# protocoles_de_comm.net
KiCad netlist of a schematic drawn in Altium Designer
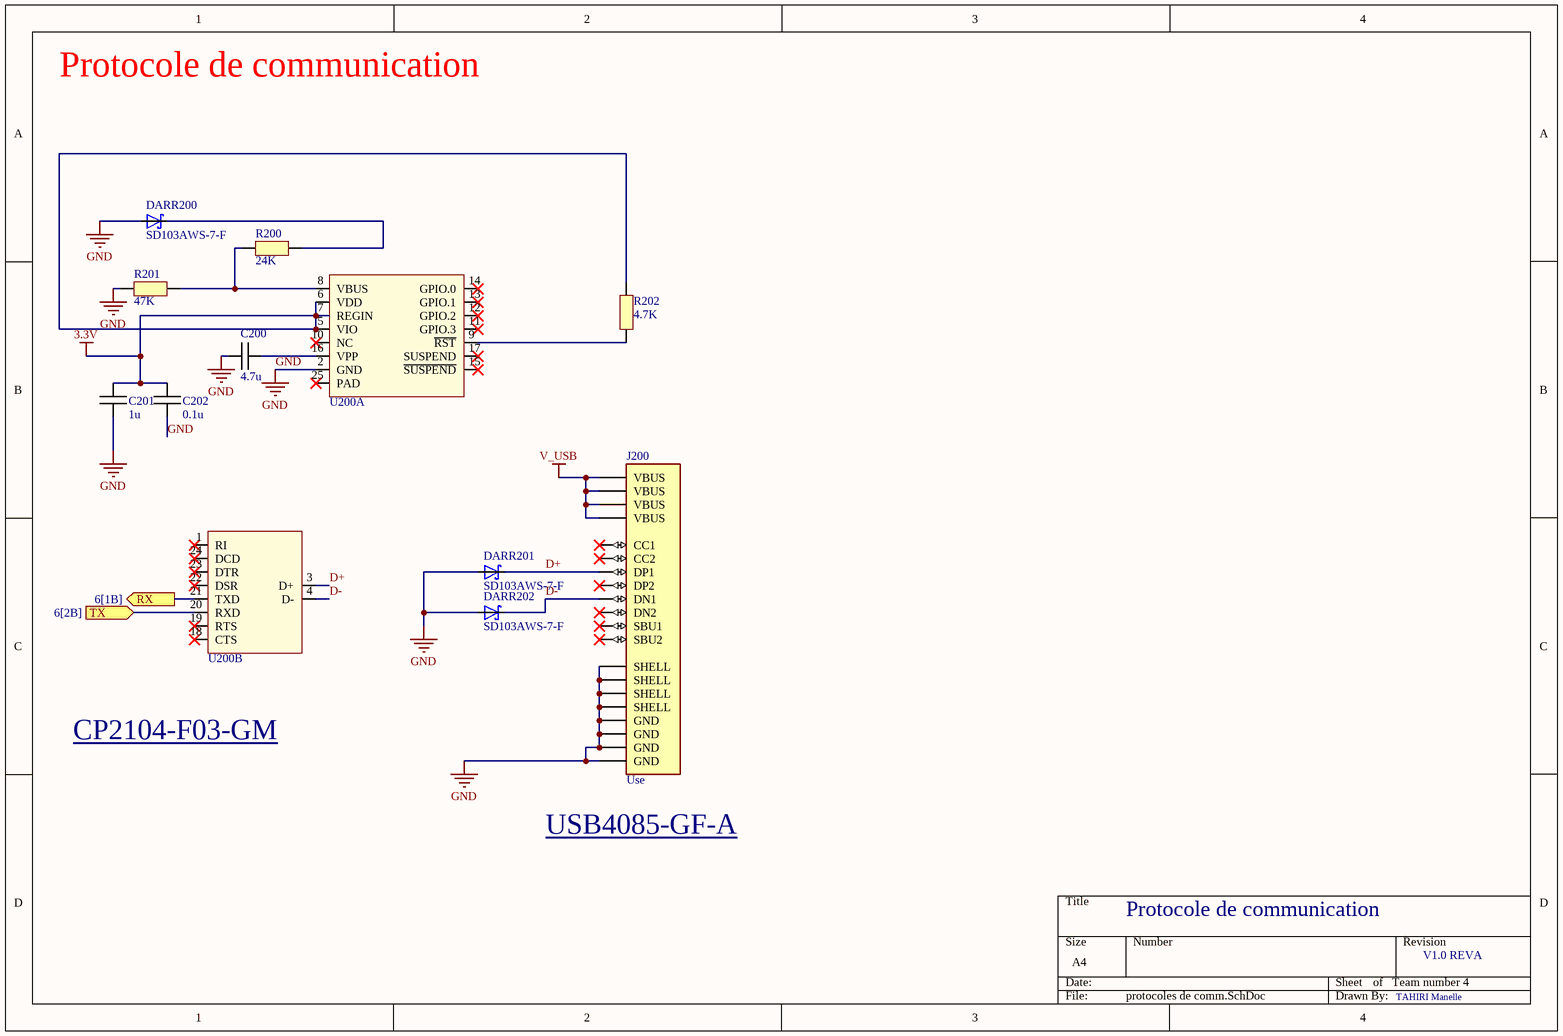
[diagram p0: protocoles de comm.SchDoc]

(export (version "E")
  (design (tool "Eeschema 10.0.6"))
  (components
    (comp (ref "C200")
      (value "4.7u")
      (footprint "CAPC1005X06N")
      (libsource (lib "SCHLibrary") (part "Capacitor"))
    )
    (comp (ref "C201")
      (value "1u")
      (footprint "CAPC1005X06N")
      (libsource (lib "SCHLibrary") (part "Capacitor"))
    )
    (comp (ref "C202")
      (value "0.1u")
      (footprint "CAPC1005X06N")
      (libsource (lib "SCHLibrary") (part "Capacitor"))
    )
    (comp (ref "DARR200")
      (value "SD103AWS-7-F")
      (footprint "SD103AWS-7-F")
      (description "Diode Array 3 Independent Schottky 40V 175mA Surface Mount 6-TSSOP, SC-88, SOT-363")
      (libsource (lib "SCHLibrary") (part "SD103AWS-7-F"))
    )
    (comp (ref "DARR201")
      (value "SD103AWS-7-F")
      (footprint "SD103AWS-7-F")
      (description "Diode Array 3 Independent Schottky 40V 175mA Surface Mount 6-TSSOP, SC-88, SOT-363")
      (libsource (lib "SCHLibrary") (part "SD103AWS-7-F"))
    )
    (comp (ref "DARR202")
      (value "SD103AWS-7-F")
      (footprint "SD103AWS-7-F")
      (description "Diode Array 3 Independent Schottky 40V 175mA Surface Mount 6-TSSOP, SC-88, SOT-363")
      (libsource (lib "SCHLibrary") (part "SD103AWS-7-F"))
    )
    (comp (ref "J200")
      (value "Use")
      (footprint "USB4085-GF-A")
      (description "Connecteurs USB USB Type C, 2.0, Rec, TH , G/F, RA , Top Mnt, T & R")
      (libsource (lib "SCHLibrary") (part "USB4085-GF-A"))
    )
    (comp (ref "R200")
      (value "24K")
      (footprint "RESC1005X06N")
      (libsource (lib "SCHLibrary") (part "Resistor"))
    )
    (comp (ref "R201")
      (value "47K")
      (footprint "RESC1005X06N")
      (libsource (lib "SCHLibrary") (part "Resistor"))
    )
    (comp (ref "R202") (value "4.7K") (footprint "RESC1005X06N") (libsource (lib "") (part "Resistor_1")))
    (comp (ref "U200")
      (value "CP2104-F03-GM")
      (footprint "PQFN50P400X400X80_HS-25N")
      (description "USB Bridge, USB to UART USB 2.0 UART Interface 24-QFN (4x4)")
      (libsource (lib "SCHLibrary") (part "USBBridge"))
    )
  )
  (nets
    (net (code "1") (name "/D+") (class "Default")
      (node (ref "DARR201") (pin "1") (pinfunction "C_1") (pintype "passive"))
      (node (ref "J200") (pin "A6") (pinfunction "DP1_A6") (pintype "bidirectional"))
      (node (ref "U200") (pin "3") (pinfunction "D+_3") (pintype "passive"))
    )
    (net (code "2") (name "/D-") (class "Default")
      (node (ref "DARR202") (pin "1") (pinfunction "C_1") (pintype "passive"))
      (node (ref "J200") (pin "A7") (pinfunction "DN1_A7") (pintype "bidirectional"))
      (node (ref "U200") (pin "4") (pinfunction "D-_4") (pintype "passive"))
    )
    (net (code "3") (name "/RX") (class "Default")
      (node (ref "U200") (pin "21") (pinfunction "TXD_21") (pintype "passive"))
    )
    (net (code "4") (name "/TX") (class "Default")
      (node (ref "U200") (pin "20") (pinfunction "RXD_20") (pintype "passive"))
    )
    (net (code "5") (name "3.3V") (class "Default")
      (node (ref "C201") (pin "2") (pinfunction "2_2") (pintype "passive"))
      (node (ref "C202") (pin "2") (pinfunction "2_2") (pintype "passive"))
      (node (ref "R202") (pin "2") (pinfunction "2_2") (pintype "passive"))
      (node (ref "U200") (pin "5") (pinfunction "VIO_5") (pintype "passive"))
      (node (ref "U200") (pin "6") (pinfunction "VDD_6") (pintype "passive"))
      (node (ref "U200") (pin "7") (pinfunction "REGIN_7") (pintype "passive"))
    )
    (net (code "6") (name "GND") (class "Default")
      (node (ref "C200") (pin "1") (pinfunction "1_1") (pintype "passive"))
      (node (ref "C201") (pin "1") (pinfunction "1_1") (pintype "passive"))
      (node (ref "C202") (pin "1") (pinfunction "1_1") (pintype "passive"))
      (node (ref "DARR200") (pin "2") (pinfunction "A_2") (pintype "passive"))
      (node (ref "DARR201") (pin "2") (pinfunction "A_2") (pintype "passive"))
      (node (ref "DARR202") (pin "2") (pinfunction "A_2") (pintype "passive"))
      (node (ref "J200") (pin "A1") (pinfunction "GND_A1") (pintype "power_in"))
      (node (ref "J200") (pin "A12") (pinfunction "GND_A12") (pintype "power_in"))
      (node (ref "J200") (pin "B1") (pinfunction "GND_B1") (pintype "power_in"))
      (node (ref "J200") (pin "B12") (pinfunction "GND_B12") (pintype "power_in"))
      (node (ref "J200") (pin "S1") (pinfunction "SHELL_S1") (pintype "passive"))
      (node (ref "J200") (pin "S2") (pinfunction "SHELL_S2") (pintype "passive"))
      (node (ref "J200") (pin "S3") (pinfunction "SHELL_S3") (pintype "passive"))
      (node (ref "J200") (pin "S4") (pinfunction "SHELL_S4") (pintype "passive"))
      (node (ref "R201") (pin "1") (pinfunction "1_1") (pintype "passive"))
      (node (ref "U200") (pin "2") (pinfunction "GND_2") (pintype "passive"))
    )
    (net (code "7") (name "Net-(DARR200-C)") (class "Default")
      (node (ref "DARR200") (pin "1") (pinfunction "C_1") (pintype "passive"))
      (node (ref "R200") (pin "2") (pinfunction "2_2") (pintype "passive"))
    )
    (net (code "8") (name "Net-(U200A-VBUS)") (class "Default")
      (node (ref "R200") (pin "1") (pinfunction "1_1") (pintype "passive"))
      (node (ref "R201") (pin "2") (pinfunction "2_2") (pintype "passive"))
      (node (ref "U200") (pin "8") (pinfunction "VBUS_8") (pintype "passive"))
    )
    (net (code "9") (name "Net-(U200A-VPP)") (class "Default")
      (node (ref "C200") (pin "2") (pinfunction "2_2") (pintype "passive"))
      (node (ref "U200") (pin "16") (pinfunction "VPP_16") (pintype "passive"))
    )
    (net (code "10") (name "Net-(U200A-~{RST})") (class "Default")
      (node (ref "R202") (pin "1") (pinfunction "1_1") (pintype "passive"))
      (node (ref "U200") (pin "9") (pinfunction "~{RST}_9") (pintype "passive"))
    )
    (net (code "11") (name "V_USB") (class "Default")
      (node (ref "J200") (pin "A4") (pinfunction "VBUS_A4") (pintype "power_in"))
      (node (ref "J200") (pin "A9") (pinfunction "VBUS_A9") (pintype "power_in"))
      (node (ref "J200") (pin "B4") (pinfunction "VBUS_B4") (pintype "power_in"))
      (node (ref "J200") (pin "B9") (pinfunction "VBUS_B9") (pintype "power_in"))
    )
    (net (code "12") (name "unconnected-(J200-CC1-PadA5)") (class "Default")
      (node (ref "J200") (pin "A5") (pinfunction "CC1_A5") (pintype "bidirectional+no_connect"))
    )
    (net (code "13") (name "unconnected-(J200-CC2-PadB5)") (class "Default")
      (node (ref "J200") (pin "B5") (pinfunction "CC2_B5") (pintype "bidirectional+no_connect"))
    )
    (net (code "14") (name "unconnected-(J200-DN2-PadB7)") (class "Default")
      (node (ref "J200") (pin "B7") (pinfunction "DN2_B7") (pintype "bidirectional+no_connect"))
    )
    (net (code "15") (name "unconnected-(J200-DP2-PadB6)") (class "Default")
      (node (ref "J200") (pin "B6") (pinfunction "DP2_B6") (pintype "bidirectional+no_connect"))
    )
    (net (code "16") (name "unconnected-(J200-SBU1-PadA8)") (class "Default")
      (node (ref "J200") (pin "A8") (pinfunction "SBU1_A8") (pintype "bidirectional+no_connect"))
    )
    (net (code "17") (name "unconnected-(J200-SBU2-PadB8)") (class "Default")
      (node (ref "J200") (pin "B8") (pinfunction "SBU2_B8") (pintype "bidirectional+no_connect"))
    )
    (net (code "18") (name "unconnected-(U200A-GPIO.0-Pad14)") (class "Default")
      (node (ref "U200") (pin "14") (pinfunction "GPIO.0_14") (pintype "passive+no_connect"))
    )
    (net (code "19") (name "unconnected-(U200A-GPIO.1-Pad13)") (class "Default")
      (node (ref "U200") (pin "13") (pinfunction "GPIO.1_13") (pintype "passive+no_connect"))
    )
    (net (code "20") (name "unconnected-(U200A-GPIO.2-Pad12)") (class "Default")
      (node (ref "U200") (pin "12") (pinfunction "GPIO.2_12") (pintype "passive+no_connect"))
    )
    (net (code "21") (name "unconnected-(U200A-GPIO.3-Pad11)") (class "Default")
      (node (ref "U200") (pin "11") (pinfunction "GPIO.3_11") (pintype "passive+no_connect"))
    )
    (net (code "22") (name "unconnected-(U200A-NC-Pad10)") (class "Default")
      (node (ref "U200") (pin "10") (pinfunction "NC_10") (pintype "passive+no_connect"))
    )
    (net (code "23") (name "unconnected-(U200A-PAD-Pad25)") (class "Default")
      (node (ref "U200") (pin "25") (pinfunction "PAD_25") (pintype "passive+no_connect"))
    )
    (net (code "24") (name "unconnected-(U200A-SUSPEND-Pad17)") (class "Default")
      (node (ref "U200") (pin "17") (pinfunction "SUSPEND_17") (pintype "passive+no_connect"))
    )
    (net (code "25") (name "unconnected-(U200A-~{SUSPEND}-Pad15)") (class "Default")
      (node (ref "U200") (pin "15") (pinfunction "~{SUSPEND}_15") (pintype "passive+no_connect"))
    )
    (net (code "26") (name "unconnected-(U200B-CTS-Pad18)") (class "Default")
      (node (ref "U200") (pin "18") (pinfunction "CTS_18") (pintype "passive+no_connect"))
    )
    (net (code "27") (name "unconnected-(U200B-DCD-Pad24)") (class "Default")
      (node (ref "U200") (pin "24") (pinfunction "DCD_24") (pintype "passive+no_connect"))
    )
    (net (code "28") (name "unconnected-(U200B-DSR-Pad22)") (class "Default")
      (node (ref "U200") (pin "22") (pinfunction "DSR_22") (pintype "passive+no_connect"))
    )
    (net (code "29") (name "unconnected-(U200B-DTR-Pad23)") (class "Default")
      (node (ref "U200") (pin "23") (pinfunction "DTR_23") (pintype "passive+no_connect"))
    )
    (net (code "30") (name "unconnected-(U200B-RI-Pad1)") (class "Default")
      (node (ref "U200") (pin "1") (pinfunction "RI_1") (pintype "passive+no_connect"))
    )
    (net (code "31") (name "unconnected-(U200B-RTS-Pad19)") (class "Default")
      (node (ref "U200") (pin "19") (pinfunction "RTS_19") (pintype "passive+no_connect"))
    )
  )
)
